# P7_CCD_CAM_BOARD_MYIR.net
KiCad netlist of a schematic drawn in Altium Designer
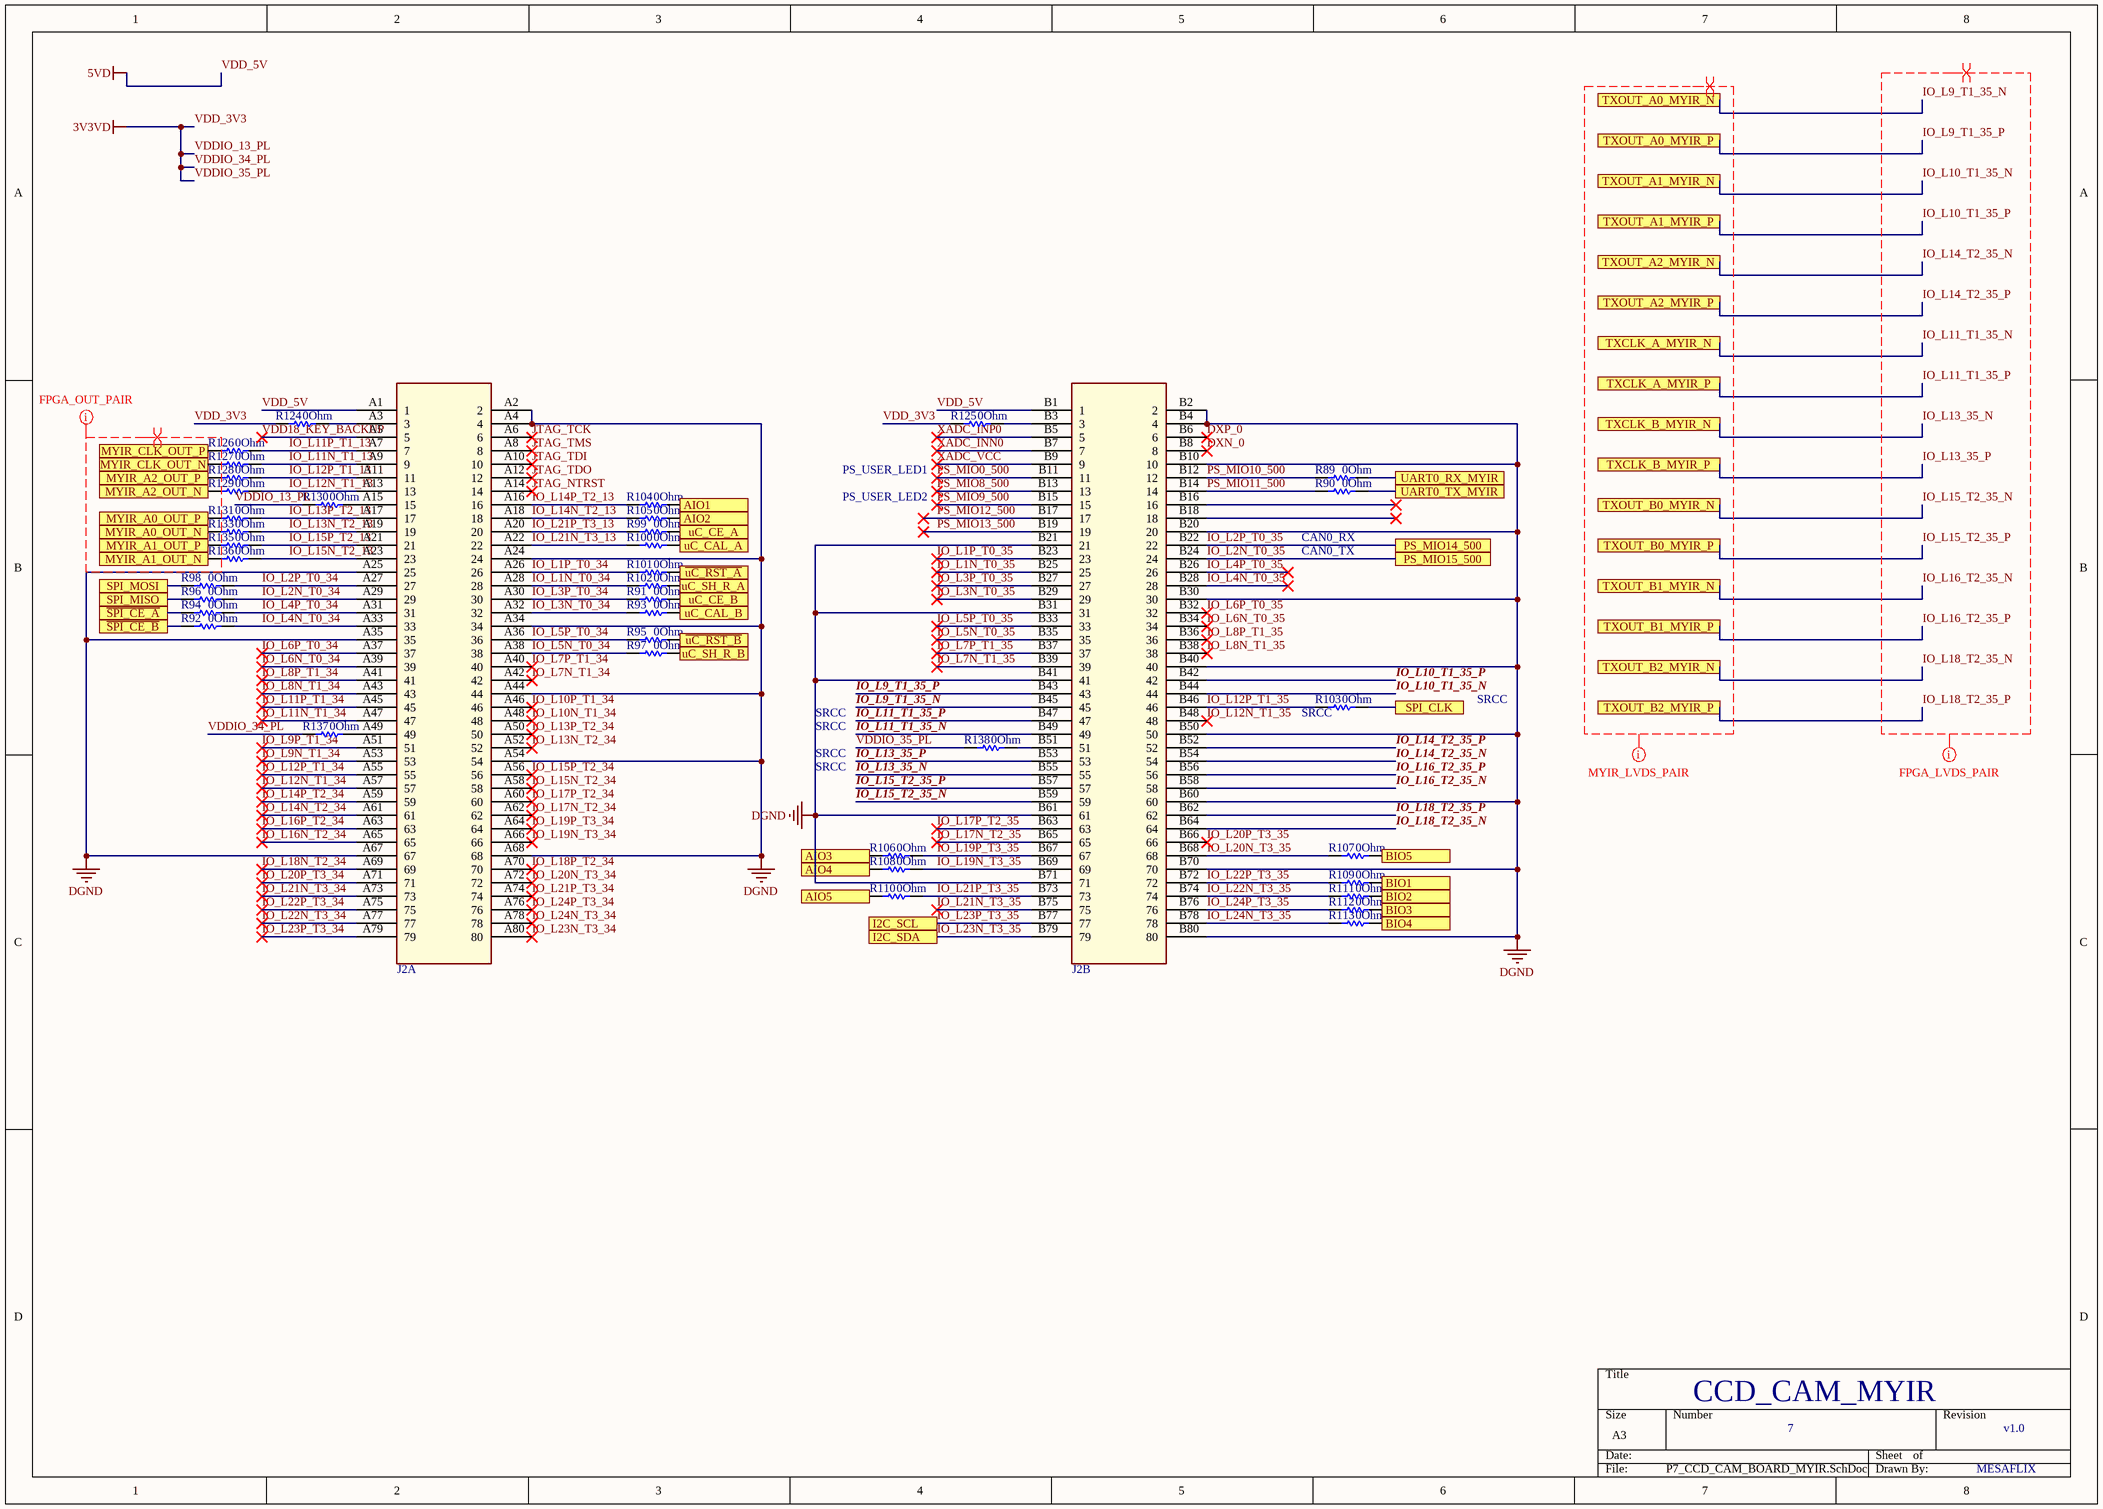
[diagram p0: P7_CCD_CAM_BOARD_MYIR.SchDoc]

(export (version "E")
  (design (tool "Eeschema 10.0.6"))
  (components
    (comp (ref "J2")
      (value "40x2 Connector 1.27mm Pitch")
      (footprint "CON2x80_MYIR_SMD")
      (fields
        (field (name "MANUFACTURER PART NUMBER") "20021121-00080T4LF")
        (field (name "DIGIKEY PART NUMBER") "609-3741-ND")
      )
      (libsource (lib "CCD_CAM_BOARD") (part "CON_40x2_MYIR_ZTURN"))
    )
    (comp (ref "R89")
      (value "0Ohm")
      (footprint "R 0402(1005)")
      (fields
        (field (name "DIGIKEYPARTNUMBER") "311-0.0LDCT-ND")
        (field (name "MANUFACTURER") "Yageo")
        (field (name "MANUFACTURERPARTNUMBER") "AC0603FR-070RL")
      )
      (libsource (lib "TESLA_PCB_LIB") (part "RES_1K_0603"))
    )
    (comp (ref "R90")
      (value "0Ohm")
      (footprint "R 0402(1005)")
      (fields
        (field (name "DIGIKEYPARTNUMBER") "311-0.0LDCT-ND")
        (field (name "MANUFACTURER") "Yageo")
        (field (name "MANUFACTURERPARTNUMBER") "AC0603FR-070RL")
      )
      (libsource (lib "TESLA_PCB_LIB") (part "RES_1K_0603"))
    )
    (comp (ref "R91")
      (value "0Ohm")
      (footprint "R 0402(1005)")
      (fields
        (field (name "DIGIKEYPARTNUMBER") "311-0.0LDCT-ND")
        (field (name "MANUFACTURER") "Yageo")
        (field (name "MANUFACTURERPARTNUMBER") "AC0603FR-070RL")
      )
      (libsource (lib "TESLA_PCB_LIB") (part "RES_1K_0603"))
    )
    (comp (ref "R92")
      (value "0Ohm")
      (footprint "R 0402(1005)")
      (fields
        (field (name "DIGIKEYPARTNUMBER") "311-0.0LDCT-ND")
        (field (name "MANUFACTURER") "Yageo")
        (field (name "MANUFACTURERPARTNUMBER") "AC0603FR-070RL")
      )
      (libsource (lib "TESLA_PCB_LIB") (part "RES_1K_0603"))
    )
    (comp (ref "R93")
      (value "0Ohm")
      (footprint "R 0402(1005)")
      (fields
        (field (name "DIGIKEYPARTNUMBER") "311-0.0LDCT-ND")
        (field (name "MANUFACTURER") "Yageo")
        (field (name "MANUFACTURERPARTNUMBER") "AC0603FR-070RL")
      )
      (libsource (lib "TESLA_PCB_LIB") (part "RES_1K_0603"))
    )
    (comp (ref "R94")
      (value "0Ohm")
      (footprint "R 0402(1005)")
      (fields
        (field (name "DIGIKEYPARTNUMBER") "311-0.0LDCT-ND")
        (field (name "MANUFACTURER") "Yageo")
        (field (name "MANUFACTURERPARTNUMBER") "AC0603FR-070RL")
      )
      (libsource (lib "TESLA_PCB_LIB") (part "RES_1K_0603"))
    )
    (comp (ref "R95")
      (value "0Ohm")
      (footprint "R 0402(1005)")
      (fields
        (field (name "DIGIKEYPARTNUMBER") "311-0.0LDCT-ND")
        (field (name "MANUFACTURER") "Yageo")
        (field (name "MANUFACTURERPARTNUMBER") "AC0603FR-070RL")
      )
      (libsource (lib "TESLA_PCB_LIB") (part "RES_1K_0603"))
    )
    (comp (ref "R96")
      (value "0Ohm")
      (footprint "R 0402(1005)")
      (fields
        (field (name "DIGIKEYPARTNUMBER") "311-0.0LDCT-ND")
        (field (name "MANUFACTURER") "Yageo")
        (field (name "MANUFACTURERPARTNUMBER") "AC0603FR-070RL")
      )
      (libsource (lib "TESLA_PCB_LIB") (part "RES_1K_0603"))
    )
    (comp (ref "R97")
      (value "0Ohm")
      (footprint "R 0402(1005)")
      (fields
        (field (name "DIGIKEYPARTNUMBER") "311-0.0LDCT-ND")
        (field (name "MANUFACTURER") "Yageo")
        (field (name "MANUFACTURERPARTNUMBER") "AC0603FR-070RL")
      )
      (libsource (lib "TESLA_PCB_LIB") (part "RES_1K_0603"))
    )
    (comp (ref "R98")
      (value "0Ohm")
      (footprint "R 0402(1005)")
      (fields
        (field (name "DIGIKEYPARTNUMBER") "311-0.0LDCT-ND")
        (field (name "MANUFACTURER") "Yageo")
        (field (name "MANUFACTURERPARTNUMBER") "AC0603FR-070RL")
      )
      (libsource (lib "TESLA_PCB_LIB") (part "RES_1K_0603"))
    )
    (comp (ref "R99")
      (value "0Ohm")
      (footprint "R 0402(1005)")
      (fields
        (field (name "DIGIKEYPARTNUMBER") "311-0.0LDCT-ND")
        (field (name "MANUFACTURER") "Yageo")
        (field (name "MANUFACTURERPARTNUMBER") "AC0603FR-070RL")
      )
      (libsource (lib "TESLA_PCB_LIB") (part "RES_1K_0603"))
    )
    (comp (ref "R100")
      (value "0Ohm")
      (footprint "R 0402(1005)")
      (fields
        (field (name "DIGIKEYPARTNUMBER") "311-0.0LDCT-ND")
        (field (name "MANUFACTURER") "Yageo")
        (field (name "MANUFACTURERPARTNUMBER") "AC0603FR-070RL")
      )
      (libsource (lib "TESLA_PCB_LIB") (part "RES_1K_0603"))
    )
    (comp (ref "R101")
      (value "0Ohm")
      (footprint "R 0402(1005)")
      (fields
        (field (name "DIGIKEYPARTNUMBER") "311-0.0LDCT-ND")
        (field (name "MANUFACTURER") "Yageo")
        (field (name "MANUFACTURERPARTNUMBER") "AC0603FR-070RL")
      )
      (libsource (lib "TESLA_PCB_LIB") (part "RES_1K_0603"))
    )
    (comp (ref "R102")
      (value "0Ohm")
      (footprint "R 0402(1005)")
      (fields
        (field (name "DIGIKEYPARTNUMBER") "311-0.0LDCT-ND")
        (field (name "MANUFACTURER") "Yageo")
        (field (name "MANUFACTURERPARTNUMBER") "AC0603FR-070RL")
      )
      (libsource (lib "TESLA_PCB_LIB") (part "RES_1K_0603"))
    )
    (comp (ref "R103")
      (value "0Ohm")
      (footprint "R 0402(1005)")
      (fields
        (field (name "DIGIKEYPARTNUMBER") "311-0.0LDCT-ND")
        (field (name "MANUFACTURER") "Yageo")
        (field (name "MANUFACTURERPARTNUMBER") "AC0603FR-070RL")
      )
      (libsource (lib "TESLA_PCB_LIB") (part "RES_1K_0603"))
    )
    (comp (ref "R104")
      (value "0Ohm")
      (footprint "R 0402(1005)")
      (fields
        (field (name "DIGIKEYPARTNUMBER") "311-0.0LDCT-ND")
        (field (name "MANUFACTURER") "Yageo")
        (field (name "MANUFACTURERPARTNUMBER") "AC0603FR-070RL")
      )
      (libsource (lib "TESLA_PCB_LIB") (part "RES_1K_0603"))
    )
    (comp (ref "R105")
      (value "0Ohm")
      (footprint "R 0402(1005)")
      (fields
        (field (name "DIGIKEYPARTNUMBER") "311-0.0LDCT-ND")
        (field (name "MANUFACTURER") "Yageo")
        (field (name "MANUFACTURERPARTNUMBER") "AC0603FR-070RL")
      )
      (libsource (lib "TESLA_PCB_LIB") (part "RES_1K_0603"))
    )
    (comp (ref "R106")
      (value "0Ohm")
      (footprint "R 0402(1005)")
      (fields
        (field (name "DIGIKEYPARTNUMBER") "311-0.0LDCT-ND")
        (field (name "MANUFACTURER") "Yageo")
        (field (name "MANUFACTURERPARTNUMBER") "AC0603FR-070RL")
      )
      (libsource (lib "TESLA_PCB_LIB") (part "RES_1K_0603"))
    )
    (comp (ref "R107")
      (value "0Ohm")
      (footprint "R 0402(1005)")
      (fields
        (field (name "DIGIKEYPARTNUMBER") "311-0.0LDCT-ND")
        (field (name "MANUFACTURER") "Yageo")
        (field (name "MANUFACTURERPARTNUMBER") "AC0603FR-070RL")
      )
      (libsource (lib "TESLA_PCB_LIB") (part "RES_1K_0603"))
    )
    (comp (ref "R108")
      (value "0Ohm")
      (footprint "R 0402(1005)")
      (fields
        (field (name "DIGIKEYPARTNUMBER") "311-0.0LDCT-ND")
        (field (name "MANUFACTURER") "Yageo")
        (field (name "MANUFACTURERPARTNUMBER") "AC0603FR-070RL")
      )
      (libsource (lib "TESLA_PCB_LIB") (part "RES_1K_0603"))
    )
    (comp (ref "R109")
      (value "0Ohm")
      (footprint "R 0402(1005)")
      (fields
        (field (name "DIGIKEYPARTNUMBER") "311-0.0LDCT-ND")
        (field (name "MANUFACTURER") "Yageo")
        (field (name "MANUFACTURERPARTNUMBER") "AC0603FR-070RL")
      )
      (libsource (lib "TESLA_PCB_LIB") (part "RES_1K_0603"))
    )
    (comp (ref "R110")
      (value "0Ohm")
      (footprint "R 0402(1005)")
      (fields
        (field (name "DIGIKEYPARTNUMBER") "311-0.0LDCT-ND")
        (field (name "MANUFACTURER") "Yageo")
        (field (name "MANUFACTURERPARTNUMBER") "AC0603FR-070RL")
      )
      (libsource (lib "TESLA_PCB_LIB") (part "RES_1K_0603"))
    )
    (comp (ref "R111")
      (value "0Ohm")
      (footprint "R 0402(1005)")
      (fields
        (field (name "DIGIKEYPARTNUMBER") "311-0.0LDCT-ND")
        (field (name "MANUFACTURER") "Yageo")
        (field (name "MANUFACTURERPARTNUMBER") "AC0603FR-070RL")
      )
      (libsource (lib "TESLA_PCB_LIB") (part "RES_1K_0603"))
    )
    (comp (ref "R112")
      (value "0Ohm")
      (footprint "R 0402(1005)")
      (fields
        (field (name "DIGIKEYPARTNUMBER") "311-0.0LDCT-ND")
        (field (name "MANUFACTURER") "Yageo")
        (field (name "MANUFACTURERPARTNUMBER") "AC0603FR-070RL")
      )
      (libsource (lib "TESLA_PCB_LIB") (part "RES_1K_0603"))
    )
    (comp (ref "R113")
      (value "0Ohm")
      (footprint "R 0402(1005)")
      (fields
        (field (name "DIGIKEYPARTNUMBER") "311-0.0LDCT-ND")
        (field (name "MANUFACTURER") "Yageo")
        (field (name "MANUFACTURERPARTNUMBER") "AC0603FR-070RL")
      )
      (libsource (lib "TESLA_PCB_LIB") (part "RES_1K_0603"))
    )
    (comp (ref "R124")
      (value "0Ohm")
      (footprint "R 0402(1005)")
      (fields
        (field (name "DIGIKEYPARTNUMBER") "311-0.0LDCT-ND")
        (field (name "MANUFACTURER") "Yageo")
        (field (name "MANUFACTURERPARTNUMBER") "AC0603FR-070RL")
      )
      (libsource (lib "TESLA_PCB_LIB") (part "RES_1K_0603"))
    )
    (comp (ref "R125")
      (value "0Ohm")
      (footprint "R 0402(1005)")
      (fields
        (field (name "DIGIKEYPARTNUMBER") "311-0.0LDCT-ND")
        (field (name "MANUFACTURER") "Yageo")
        (field (name "MANUFACTURERPARTNUMBER") "AC0603FR-070RL")
      )
      (libsource (lib "TESLA_PCB_LIB") (part "RES_1K_0603"))
    )
    (comp (ref "R126")
      (value "0Ohm")
      (footprint "R 0402(1005)")
      (fields
        (field (name "DIGIKEYPARTNUMBER") "311-0.0LDCT-ND")
        (field (name "MANUFACTURER") "Yageo")
        (field (name "MANUFACTURERPARTNUMBER") "AC0603FR-070RL")
      )
      (libsource (lib "TESLA_PCB_LIB") (part "RES_1K_0603"))
    )
    (comp (ref "R127")
      (value "0Ohm")
      (footprint "R 0402(1005)")
      (fields
        (field (name "DIGIKEYPARTNUMBER") "311-0.0LDCT-ND")
        (field (name "MANUFACTURER") "Yageo")
        (field (name "MANUFACTURERPARTNUMBER") "AC0603FR-070RL")
      )
      (libsource (lib "TESLA_PCB_LIB") (part "RES_1K_0603"))
    )
    (comp (ref "R128")
      (value "0Ohm")
      (footprint "R 0402(1005)")
      (fields
        (field (name "DIGIKEYPARTNUMBER") "311-0.0LDCT-ND")
        (field (name "MANUFACTURER") "Yageo")
        (field (name "MANUFACTURERPARTNUMBER") "AC0603FR-070RL")
      )
      (libsource (lib "TESLA_PCB_LIB") (part "RES_1K_0603"))
    )
    (comp (ref "R129")
      (value "0Ohm")
      (footprint "R 0402(1005)")
      (fields
        (field (name "DIGIKEYPARTNUMBER") "311-0.0LDCT-ND")
        (field (name "MANUFACTURER") "Yageo")
        (field (name "MANUFACTURERPARTNUMBER") "AC0603FR-070RL")
      )
      (libsource (lib "TESLA_PCB_LIB") (part "RES_1K_0603"))
    )
    (comp (ref "R130")
      (value "0Ohm")
      (footprint "R 0402(1005)")
      (fields
        (field (name "DIGIKEYPARTNUMBER") "311-0.0LDCT-ND")
        (field (name "MANUFACTURER") "Yageo")
        (field (name "MANUFACTURERPARTNUMBER") "AC0603FR-070RL")
      )
      (libsource (lib "TESLA_PCB_LIB") (part "RES_1K_0603"))
    )
    (comp (ref "R131")
      (value "0Ohm")
      (footprint "R 0402(1005)")
      (fields
        (field (name "DIGIKEYPARTNUMBER") "311-0.0LDCT-ND")
        (field (name "MANUFACTURER") "Yageo")
        (field (name "MANUFACTURERPARTNUMBER") "AC0603FR-070RL")
      )
      (libsource (lib "TESLA_PCB_LIB") (part "RES_1K_0603"))
    )
    (comp (ref "R133")
      (value "0Ohm")
      (footprint "R 0402(1005)")
      (fields
        (field (name "DIGIKEYPARTNUMBER") "311-0.0LDCT-ND")
        (field (name "MANUFACTURER") "Yageo")
        (field (name "MANUFACTURERPARTNUMBER") "AC0603FR-070RL")
      )
      (libsource (lib "TESLA_PCB_LIB") (part "RES_1K_0603"))
    )
    (comp (ref "R135")
      (value "0Ohm")
      (footprint "R 0402(1005)")
      (fields
        (field (name "DIGIKEYPARTNUMBER") "311-0.0LDCT-ND")
        (field (name "MANUFACTURER") "Yageo")
        (field (name "MANUFACTURERPARTNUMBER") "AC0603FR-070RL")
      )
      (libsource (lib "TESLA_PCB_LIB") (part "RES_1K_0603"))
    )
    (comp (ref "R136")
      (value "0Ohm")
      (footprint "R 0402(1005)")
      (fields
        (field (name "DIGIKEYPARTNUMBER") "311-0.0LDCT-ND")
        (field (name "MANUFACTURER") "Yageo")
        (field (name "MANUFACTURERPARTNUMBER") "AC0603FR-070RL")
      )
      (libsource (lib "TESLA_PCB_LIB") (part "RES_1K_0603"))
    )
    (comp (ref "R137")
      (value "0Ohm")
      (footprint "R 0402(1005)")
      (fields
        (field (name "DIGIKEYPARTNUMBER") "311-0.0LDCT-ND")
        (field (name "MANUFACTURER") "Yageo")
        (field (name "MANUFACTURERPARTNUMBER") "AC0603FR-070RL")
      )
      (libsource (lib "TESLA_PCB_LIB") (part "RES_1K_0603"))
    )
    (comp (ref "R138")
      (value "0Ohm")
      (footprint "R 0402(1005)")
      (fields
        (field (name "DIGIKEYPARTNUMBER") "311-0.0LDCT-ND")
        (field (name "MANUFACTURER") "Yageo")
        (field (name "MANUFACTURERPARTNUMBER") "AC0603FR-070RL")
      )
      (libsource (lib "TESLA_PCB_LIB") (part "RES_1K_0603"))
    )
  )
  (nets
    (net (code "1") (name "/AIO1") (class "Default")
      (node (ref "R104") (pin "2") (pinfunction "2_2") (pintype "passive"))
    )
    (net (code "2") (name "/AIO2") (class "Default")
      (node (ref "R105") (pin "2") (pinfunction "2_2") (pintype "passive"))
    )
    (net (code "3") (name "/AIO3") (class "Default")
      (node (ref "R106") (pin "1") (pinfunction "1_1") (pintype "passive"))
    )
    (net (code "4") (name "/AIO4") (class "Default")
      (node (ref "R108") (pin "1") (pinfunction "1_1") (pintype "passive"))
    )
    (net (code "5") (name "/AIO5") (class "Default")
      (node (ref "R110") (pin "1") (pinfunction "1_1") (pintype "passive"))
    )
    (net (code "6") (name "/BIO1") (class "Default")
      (node (ref "R109") (pin "2") (pinfunction "2_2") (pintype "passive"))
    )
    (net (code "7") (name "/BIO2") (class "Default")
      (node (ref "R111") (pin "2") (pinfunction "2_2") (pintype "passive"))
    )
    (net (code "8") (name "/BIO3") (class "Default")
      (node (ref "R112") (pin "2") (pinfunction "2_2") (pintype "passive"))
    )
    (net (code "9") (name "/BIO4") (class "Default")
      (node (ref "R113") (pin "2") (pinfunction "2_2") (pintype "passive"))
    )
    (net (code "10") (name "/BIO5") (class "Default")
      (node (ref "R107") (pin "2") (pinfunction "2_2") (pintype "passive"))
    )
    (net (code "11") (name "/DXN_0") (class "Default")
      (node (ref "J2") (pin "B8") (pinfunction "8_B8") (pintype "passive+no_connect"))
    )
    (net (code "12") (name "/DXP_0") (class "Default")
      (node (ref "J2") (pin "B6") (pinfunction "6_B6") (pintype "passive+no_connect"))
    )
    (net (code "13") (name "/IO_L1N_T0_34") (class "Default")
      (node (ref "J2") (pin "A28") (pinfunction "28_A28") (pintype "passive"))
      (node (ref "R102") (pin "1") (pinfunction "1_1") (pintype "passive"))
    )
    (net (code "14") (name "/IO_L1N_T0_35") (class "Default")
      (node (ref "J2") (pin "B25") (pinfunction "25_B25") (pintype "passive+no_connect"))
    )
    (net (code "15") (name "/IO_L1P_T0_34") (class "Default")
      (node (ref "J2") (pin "A26") (pinfunction "26_A26") (pintype "passive"))
      (node (ref "R101") (pin "1") (pinfunction "1_1") (pintype "passive"))
    )
    (net (code "16") (name "/IO_L1P_T0_35") (class "Default")
      (node (ref "J2") (pin "B23") (pinfunction "23_B23") (pintype "passive+no_connect"))
    )
    (net (code "17") (name "/IO_L2N_T0_34") (class "Default")
      (node (ref "J2") (pin "A29") (pinfunction "29_A29") (pintype "passive"))
      (node (ref "R96") (pin "2") (pinfunction "2_2") (pintype "passive"))
    )
    (net (code "18") (name "/IO_L2N_T0_35") (class "Default")
      (node (ref "J2") (pin "B24") (pinfunction "24_B24") (pintype "passive"))
    )
    (net (code "19") (name "/IO_L2P_T0_34") (class "Default")
      (node (ref "J2") (pin "A27") (pinfunction "27_A27") (pintype "passive"))
      (node (ref "R98") (pin "2") (pinfunction "2_2") (pintype "passive"))
    )
    (net (code "20") (name "/IO_L2P_T0_35") (class "Default")
      (node (ref "J2") (pin "B22") (pinfunction "22_B22") (pintype "passive"))
    )
    (net (code "21") (name "/IO_L3N_T0_34") (class "Default")
      (node (ref "J2") (pin "A32") (pinfunction "32_A32") (pintype "passive"))
      (node (ref "R93") (pin "1") (pinfunction "1_1") (pintype "passive"))
    )
    (net (code "22") (name "/IO_L3N_T0_35") (class "Default")
      (node (ref "J2") (pin "B29") (pinfunction "29_B29") (pintype "passive+no_connect"))
    )
    (net (code "23") (name "/IO_L3P_T0_34") (class "Default")
      (node (ref "J2") (pin "A30") (pinfunction "30_A30") (pintype "passive"))
      (node (ref "R91") (pin "1") (pinfunction "1_1") (pintype "passive"))
    )
    (net (code "24") (name "/IO_L3P_T0_35") (class "Default")
      (node (ref "J2") (pin "B27") (pinfunction "27_B27") (pintype "passive+no_connect"))
    )
    (net (code "25") (name "/IO_L4N_T0_34") (class "Default")
      (node (ref "J2") (pin "A33") (pinfunction "33_A33") (pintype "passive"))
      (node (ref "R92") (pin "2") (pinfunction "2_2") (pintype "passive"))
    )
    (net (code "26") (name "/IO_L4N_T0_35") (class "Default")
      (node (ref "J2") (pin "B28") (pinfunction "28_B28") (pintype "passive+no_connect"))
    )
    (net (code "27") (name "/IO_L4P_T0_34") (class "Default")
      (node (ref "J2") (pin "A31") (pinfunction "31_A31") (pintype "passive"))
      (node (ref "R94") (pin "2") (pinfunction "2_2") (pintype "passive"))
    )
    (net (code "28") (name "/IO_L4P_T0_35") (class "Default")
      (node (ref "J2") (pin "B26") (pinfunction "26_B26") (pintype "passive+no_connect"))
    )
    (net (code "29") (name "/IO_L5N_T0_34") (class "Default")
      (node (ref "J2") (pin "A38") (pinfunction "38_A38") (pintype "passive"))
      (node (ref "R97") (pin "1") (pinfunction "1_1") (pintype "passive"))
    )
    (net (code "30") (name "/IO_L5N_T0_35") (class "Default")
      (node (ref "J2") (pin "B35") (pinfunction "35_B35") (pintype "passive+no_connect"))
    )
    (net (code "31") (name "/IO_L5P_T0_34") (class "Default")
      (node (ref "J2") (pin "A36") (pinfunction "36_A36") (pintype "passive"))
      (node (ref "R95") (pin "1") (pinfunction "1_1") (pintype "passive"))
    )
    (net (code "32") (name "/IO_L5P_T0_35") (class "Default")
      (node (ref "J2") (pin "B33") (pinfunction "33_B33") (pintype "passive+no_connect"))
    )
    (net (code "33") (name "/IO_L6N_T0_34") (class "Default")
      (node (ref "J2") (pin "A39") (pinfunction "39_A39") (pintype "passive+no_connect"))
    )
    (net (code "34") (name "/IO_L6N_T0_35") (class "Default")
      (node (ref "J2") (pin "B34") (pinfunction "34_B34") (pintype "passive+no_connect"))
    )
    (net (code "35") (name "/IO_L6P_T0_34") (class "Default")
      (node (ref "J2") (pin "A37") (pinfunction "37_A37") (pintype "passive+no_connect"))
    )
    (net (code "36") (name "/IO_L6P_T0_35") (class "Default")
      (node (ref "J2") (pin "B32") (pinfunction "32_B32") (pintype "passive+no_connect"))
    )
    (net (code "37") (name "/IO_L7N_T1_34") (class "Default")
      (node (ref "J2") (pin "A42") (pinfunction "42_A42") (pintype "passive+no_connect"))
    )
    (net (code "38") (name "/IO_L7N_T1_35") (class "Default")
      (node (ref "J2") (pin "B39") (pinfunction "39_B39") (pintype "passive+no_connect"))
    )
    (net (code "39") (name "/IO_L7P_T1_34") (class "Default")
      (node (ref "J2") (pin "A40") (pinfunction "40_A40") (pintype "passive+no_connect"))
    )
    (net (code "40") (name "/IO_L7P_T1_35") (class "Default")
      (node (ref "J2") (pin "B37") (pinfunction "37_B37") (pintype "passive+no_connect"))
    )
    (net (code "41") (name "/IO_L8N_T1_34") (class "Default")
      (node (ref "J2") (pin "A43") (pinfunction "43_A43") (pintype "passive+no_connect"))
    )
    (net (code "42") (name "/IO_L8N_T1_35") (class "Default")
      (node (ref "J2") (pin "B38") (pinfunction "38_B38") (pintype "passive+no_connect"))
    )
    (net (code "43") (name "/IO_L8P_T1_34") (class "Default")
      (node (ref "J2") (pin "A41") (pinfunction "41_A41") (pintype "passive+no_connect"))
    )
    (net (code "44") (name "/IO_L8P_T1_35") (class "Default")
      (node (ref "J2") (pin "B36") (pinfunction "36_B36") (pintype "passive+no_connect"))
    )
    (net (code "45") (name "/IO_L9N_T1_34") (class "Default")
      (node (ref "J2") (pin "A53") (pinfunction "53_A53") (pintype "passive+no_connect"))
    )
    (net (code "46") (name "/IO_L9P_T1_34") (class "Default")
      (node (ref "J2") (pin "A51") (pinfunction "51_A51") (pintype "passive+no_connect"))
    )
    (net (code "47") (name "/IO_L9_T1_35_N") (class "Default")
      (node (ref "J2") (pin "B45") (pinfunction "45_B45") (pintype "passive"))
    )
    (net (code "48") (name "/IO_L9_T1_35_P") (class "Default")
      (node (ref "J2") (pin "B43") (pinfunction "43_B43") (pintype "passive"))
    )
    (net (code "49") (name "/IO_L10N_T1_34") (class "Default")
      (node (ref "J2") (pin "A48") (pinfunction "48_A48") (pintype "passive+no_connect"))
    )
    (net (code "50") (name "/IO_L10P_T1_34") (class "Default")
      (node (ref "J2") (pin "A46") (pinfunction "46_A46") (pintype "passive+no_connect"))
    )
    (net (code "51") (name "/IO_L10_T1_35_N") (class "Default")
      (node (ref "J2") (pin "B44") (pinfunction "44_B44") (pintype "passive"))
    )
    (net (code "52") (name "/IO_L10_T1_35_P") (class "Default")
      (node (ref "J2") (pin "B42") (pinfunction "42_B42") (pintype "passive"))
    )
    (net (code "53") (name "/IO_L11N_T1_13") (class "Default")
      (node (ref "J2") (pin "A9") (pinfunction "9_A9") (pintype "passive"))
      (node (ref "R127") (pin "2") (pinfunction "2_2") (pintype "passive"))
    )
    (net (code "54") (name "/IO_L11N_T1_34") (class "Default")
      (node (ref "J2") (pin "A47") (pinfunction "47_A47") (pintype "passive+no_connect"))
    )
    (net (code "55") (name "/IO_L11P_T1_13") (class "Default")
      (node (ref "J2") (pin "A7") (pinfunction "7_A7") (pintype "passive"))
      (node (ref "R126") (pin "2") (pinfunction "2_2") (pintype "passive"))
    )
    (net (code "56") (name "/IO_L11P_T1_34") (class "Default")
      (node (ref "J2") (pin "A45") (pinfunction "45_A45") (pintype "passive+no_connect"))
    )
    (net (code "57") (name "/IO_L11_T1_35_N") (class "Default")
      (node (ref "J2") (pin "B49") (pinfunction "49_B49") (pintype "passive"))
    )
    (net (code "58") (name "/IO_L11_T1_35_P") (class "Default")
      (node (ref "J2") (pin "B47") (pinfunction "47_B47") (pintype "passive"))
    )
    (net (code "59") (name "/IO_L12N_T1_13") (class "Default")
      (node (ref "J2") (pin "A13") (pinfunction "13_A13") (pintype "passive"))
      (node (ref "R129") (pin "2") (pinfunction "2_2") (pintype "passive"))
    )
    (net (code "60") (name "/IO_L12N_T1_34") (class "Default")
      (node (ref "J2") (pin "A57") (pinfunction "57_A57") (pintype "passive+no_connect"))
    )
    (net (code "61") (name "/IO_L12N_T1_35") (class "Default")
      (node (ref "J2") (pin "B48") (pinfunction "48_B48") (pintype "passive+no_connect"))
    )
    (net (code "62") (name "/IO_L12P_T1_13") (class "Default")
      (node (ref "J2") (pin "A11") (pinfunction "11_A11") (pintype "passive"))
      (node (ref "R128") (pin "2") (pinfunction "2_2") (pintype "passive"))
    )
    (net (code "63") (name "/IO_L12P_T1_34") (class "Default")
      (node (ref "J2") (pin "A55") (pinfunction "55_A55") (pintype "passive+no_connect"))
    )
    (net (code "64") (name "/IO_L12P_T1_35") (class "Default")
      (node (ref "J2") (pin "B46") (pinfunction "46_B46") (pintype "passive"))
      (node (ref "R103") (pin "1") (pinfunction "1_1") (pintype "passive"))
    )
    (net (code "65") (name "/IO_L13N_T2_13") (class "Default")
      (node (ref "J2") (pin "A19") (pinfunction "19_A19") (pintype "passive"))
      (node (ref "R133") (pin "2") (pinfunction "2_2") (pintype "passive"))
    )
    (net (code "66") (name "/IO_L13N_T2_34") (class "Default")
      (node (ref "J2") (pin "A52") (pinfunction "52_A52") (pintype "passive+no_connect"))
    )
    (net (code "67") (name "/IO_L13P_T2_13") (class "Default")
      (node (ref "J2") (pin "A17") (pinfunction "17_A17") (pintype "passive"))
      (node (ref "R131") (pin "2") (pinfunction "2_2") (pintype "passive"))
    )
    (net (code "68") (name "/IO_L13P_T2_34") (class "Default")
      (node (ref "J2") (pin "A50") (pinfunction "50_A50") (pintype "passive+no_connect"))
    )
    (net (code "69") (name "/IO_L13_35_N") (class "Default")
      (node (ref "J2") (pin "B55") (pinfunction "55_B55") (pintype "passive"))
    )
    (net (code "70") (name "/IO_L13_35_P") (class "Default")
      (node (ref "J2") (pin "B53") (pinfunction "53_B53") (pintype "passive"))
    )
    (net (code "71") (name "/IO_L14N_T2_13") (class "Default")
      (node (ref "J2") (pin "A18") (pinfunction "18_A18") (pintype "passive"))
      (node (ref "R105") (pin "1") (pinfunction "1_1") (pintype "passive"))
    )
    (net (code "72") (name "/IO_L14N_T2_34") (class "Default")
      (node (ref "J2") (pin "A61") (pinfunction "61_A61") (pintype "passive+no_connect"))
    )
    (net (code "73") (name "/IO_L14P_T2_13") (class "Default")
      (node (ref "J2") (pin "A16") (pinfunction "16_A16") (pintype "passive"))
      (node (ref "R104") (pin "1") (pinfunction "1_1") (pintype "passive"))
    )
    (net (code "74") (name "/IO_L14P_T2_34") (class "Default")
      (node (ref "J2") (pin "A59") (pinfunction "59_A59") (pintype "passive+no_connect"))
    )
    (net (code "75") (name "/IO_L14_T2_35_N") (class "Default")
      (node (ref "J2") (pin "B54") (pinfunction "54_B54") (pintype "passive"))
    )
    (net (code "76") (name "/IO_L14_T2_35_P") (class "Default")
      (node (ref "J2") (pin "B52") (pinfunction "52_B52") (pintype "passive"))
    )
    (net (code "77") (name "/IO_L15N_T2_13") (class "Default")
      (node (ref "J2") (pin "A23") (pinfunction "23_A23") (pintype "passive"))
      (node (ref "R136") (pin "2") (pinfunction "2_2") (pintype "passive"))
    )
    (net (code "78") (name "/IO_L15N_T2_34") (class "Default")
      (node (ref "J2") (pin "A58") (pinfunction "58_A58") (pintype "passive+no_connect"))
    )
    (net (code "79") (name "/IO_L15P_T2_13") (class "Default")
      (node (ref "J2") (pin "A21") (pinfunction "21_A21") (pintype "passive"))
      (node (ref "R135") (pin "2") (pinfunction "2_2") (pintype "passive"))
    )
    (net (code "80") (name "/IO_L15P_T2_34") (class "Default")
      (node (ref "J2") (pin "A56") (pinfunction "56_A56") (pintype "passive+no_connect"))
    )
    (net (code "81") (name "/IO_L15_T2_35_N") (class "Default")
      (node (ref "J2") (pin "B59") (pinfunction "59_B59") (pintype "passive"))
    )
    (net (code "82") (name "/IO_L15_T2_35_P") (class "Default")
      (node (ref "J2") (pin "B57") (pinfunction "57_B57") (pintype "passive"))
    )
    (net (code "83") (name "/IO_L16N_T2_34") (class "Default")
      (node (ref "J2") (pin "A65") (pinfunction "65_A65") (pintype "passive+no_connect"))
    )
    (net (code "84") (name "/IO_L16P_T2_34") (class "Default")
      (node (ref "J2") (pin "A63") (pinfunction "63_A63") (pintype "passive+no_connect"))
    )
    (net (code "85") (name "/IO_L16_T2_35_N") (class "Default")
      (node (ref "J2") (pin "B58") (pinfunction "58_B58") (pintype "passive"))
    )
    (net (code "86") (name "/IO_L16_T2_35_P") (class "Default")
      (node (ref "J2") (pin "B56") (pinfunction "56_B56") (pintype "passive"))
    )
    (net (code "87") (name "/IO_L17N_T2_34") (class "Default")
      (node (ref "J2") (pin "A62") (pinfunction "62_A62") (pintype "passive+no_connect"))
    )
    (net (code "88") (name "/IO_L17N_T2_35") (class "Default")
      (node (ref "J2") (pin "B65") (pinfunction "65_B65") (pintype "passive+no_connect"))
    )
    (net (code "89") (name "/IO_L17P_T2_34") (class "Default")
      (node (ref "J2") (pin "A60") (pinfunction "60_A60") (pintype "passive+no_connect"))
    )
    (net (code "90") (name "/IO_L17P_T2_35") (class "Default")
      (node (ref "J2") (pin "B63") (pinfunction "63_B63") (pintype "passive+no_connect"))
    )
    (net (code "91") (name "/IO_L18N_T2_34") (class "Default")
      (node (ref "J2") (pin "A69") (pinfunction "69_A69") (pintype "passive+no_connect"))
    )
    (net (code "92") (name "/IO_L18P_T2_34") (class "Default")
      (node (ref "J2") (pin "A70") (pinfunction "70_A70") (pintype "passive+no_connect"))
    )
    (net (code "93") (name "/IO_L18_T2_35_N") (class "Default")
      (node (ref "J2") (pin "B64") (pinfunction "64_B64") (pintype "passive"))
    )
    (net (code "94") (name "/IO_L18_T2_35_P") (class "Default")
      (node (ref "J2") (pin "B62") (pinfunction "62_B62") (pintype "passive"))
    )
    (net (code "95") (name "/IO_L19N_T3_34") (class "Default")
      (node (ref "J2") (pin "A66") (pinfunction "66_A66") (pintype "passive+no_connect"))
    )
    (net (code "96") (name "/IO_L19N_T3_35") (class "Default")
      (node (ref "J2") (pin "B69") (pinfunction "69_B69") (pintype "passive"))
      (node (ref "R108") (pin "2") (pinfunction "2_2") (pintype "passive"))
    )
    (net (code "97") (name "/IO_L19P_T3_34") (class "Default")
      (node (ref "J2") (pin "A64") (pinfunction "64_A64") (pintype "passive+no_connect"))
    )
    (net (code "98") (name "/IO_L19P_T3_35") (class "Default")
      (node (ref "J2") (pin "B67") (pinfunction "67_B67") (pintype "passive"))
      (node (ref "R106") (pin "2") (pinfunction "2_2") (pintype "passive"))
    )
    (net (code "99") (name "/IO_L20N_T3_34") (class "Default")
      (node (ref "J2") (pin "A72") (pinfunction "72_A72") (pintype "passive+no_connect"))
    )
    (net (code "100") (name "/IO_L20N_T3_35") (class "Default")
      (node (ref "J2") (pin "B68") (pinfunction "68_B68") (pintype "passive"))
      (node (ref "R107") (pin "1") (pinfunction "1_1") (pintype "passive"))
    )
    (net (code "101") (name "/IO_L20P_T3_34") (class "Default")
      (node (ref "J2") (pin "A71") (pinfunction "71_A71") (pintype "passive+no_connect"))
    )
    (net (code "102") (name "/IO_L20P_T3_35") (class "Default")
      (node (ref "J2") (pin "B66") (pinfunction "66_B66") (pintype "passive+no_connect"))
    )
    (net (code "103") (name "/IO_L21N_T3_13") (class "Default")
      (node (ref "J2") (pin "A22") (pinfunction "22_A22") (pintype "passive"))
      (node (ref "R100") (pin "1") (pinfunction "1_1") (pintype "passive"))
    )
    (net (code "104") (name "/IO_L21N_T3_34") (class "Default")
      (node (ref "J2") (pin "A73") (pinfunction "73_A73") (pintype "passive+no_connect"))
    )
    (net (code "105") (name "/IO_L21N_T3_35") (class "Default")
      (node (ref "J2") (pin "B75") (pinfunction "75_B75") (pintype "passive+no_connect"))
    )
    (net (code "106") (name "/IO_L21P_T3_13") (class "Default")
      (node (ref "J2") (pin "A20") (pinfunction "20_A20") (pintype "passive"))
      (node (ref "R99") (pin "1") (pinfunction "1_1") (pintype "passive"))
    )
    (net (code "107") (name "/IO_L21P_T3_34") (class "Default")
      (node (ref "J2") (pin "A74") (pinfunction "74_A74") (pintype "passive+no_connect"))
    )
    (net (code "108") (name "/IO_L21P_T3_35") (class "Default")
      (node (ref "J2") (pin "B73") (pinfunction "73_B73") (pintype "passive"))
      (node (ref "R110") (pin "2") (pinfunction "2_2") (pintype "passive"))
    )
    (net (code "109") (name "/IO_L22N_T3_34") (class "Default")
      (node (ref "J2") (pin "A77") (pinfunction "77_A77") (pintype "passive+no_connect"))
    )
    (net (code "110") (name "/IO_L22N_T3_35") (class "Default")
      (node (ref "J2") (pin "B74") (pinfunction "74_B74") (pintype "passive"))
      (node (ref "R111") (pin "1") (pinfunction "1_1") (pintype "passive"))
    )
    (net (code "111") (name "/IO_L22P_T3_34") (class "Default")
      (node (ref "J2") (pin "A75") (pinfunction "75_A75") (pintype "passive+no_connect"))
    )
    (net (code "112") (name "/IO_L22P_T3_35") (class "Default")
      (node (ref "J2") (pin "B72") (pinfunction "72_B72") (pintype "passive"))
      (node (ref "R109") (pin "1") (pinfunction "1_1") (pintype "passive"))
    )
    (net (code "113") (name "/IO_L23N_T3_34") (class "Default")
      (node (ref "J2") (pin "A80") (pinfunction "80_A80") (pintype "passive+no_connect"))
    )
    (net (code "114") (name "/IO_L23N_T3_35") (class "Default")
      (node (ref "J2") (pin "B79") (pinfunction "79_B79") (pintype "passive"))
    )
    (net (code "115") (name "/IO_L23P_T3_34") (class "Default")
      (node (ref "J2") (pin "A79") (pinfunction "79_A79") (pintype "passive+no_connect"))
    )
    (net (code "116") (name "/IO_L23P_T3_35") (class "Default")
      (node (ref "J2") (pin "B77") (pinfunction "77_B77") (pintype "passive"))
    )
    (net (code "117") (name "/IO_L24N_T3_34") (class "Default")
      (node (ref "J2") (pin "A78") (pinfunction "78_A78") (pintype "passive+no_connect"))
    )
    (net (code "118") (name "/IO_L24N_T3_35") (class "Default")
      (node (ref "J2") (pin "B78") (pinfunction "78_B78") (pintype "passive"))
      (node (ref "R113") (pin "1") (pinfunction "1_1") (pintype "passive"))
    )
    (net (code "119") (name "/IO_L24P_T3_34") (class "Default")
      (node (ref "J2") (pin "A76") (pinfunction "76_A76") (pintype "passive+no_connect"))
    )
    (net (code "120") (name "/IO_L24P_T3_35") (class "Default")
      (node (ref "J2") (pin "B76") (pinfunction "76_B76") (pintype "passive"))
      (node (ref "R112") (pin "1") (pinfunction "1_1") (pintype "passive"))
    )
    (net (code "121") (name "/JTAG_NTRST") (class "Default")
      (node (ref "J2") (pin "A14") (pinfunction "14_A14") (pintype "passive+no_connect"))
    )
    (net (code "122") (name "/JTAG_TCK") (class "Default")
      (node (ref "J2") (pin "A6") (pinfunction "6_A6") (pintype "passive+no_connect"))
    )
    (net (code "123") (name "/JTAG_TDI") (class "Default")
      (node (ref "J2") (pin "A10") (pinfunction "10_A10") (pintype "passive+no_connect"))
    )
    (net (code "124") (name "/JTAG_TDO") (class "Default")
      (node (ref "J2") (pin "A12") (pinfunction "12_A12") (pintype "passive+no_connect"))
    )
    (net (code "125") (name "/JTAG_TMS") (class "Default")
      (node (ref "J2") (pin "A8") (pinfunction "8_A8") (pintype "passive+no_connect"))
    )
    (net (code "126") (name "/MYIR_A0_OUT_N") (class "Default")
      (node (ref "R133") (pin "1") (pinfunction "1_1") (pintype "passive"))
    )
    (net (code "127") (name "/MYIR_A0_OUT_P") (class "Default")
      (node (ref "R131") (pin "1") (pinfunction "1_1") (pintype "passive"))
    )
    (net (code "128") (name "/MYIR_A1_OUT_N") (class "Default")
      (node (ref "R136") (pin "1") (pinfunction "1_1") (pintype "passive"))
    )
    (net (code "129") (name "/MYIR_A1_OUT_P") (class "Default")
      (node (ref "R135") (pin "1") (pinfunction "1_1") (pintype "passive"))
    )
    (net (code "130") (name "/MYIR_A2_OUT_N") (class "Default")
      (node (ref "R129") (pin "1") (pinfunction "1_1") (pintype "passive"))
    )
    (net (code "131") (name "/MYIR_A2_OUT_P") (class "Default")
      (node (ref "R128") (pin "1") (pinfunction "1_1") (pintype "passive"))
    )
    (net (code "132") (name "/MYIR_CLK_OUT_N") (class "Default")
      (node (ref "R127") (pin "1") (pinfunction "1_1") (pintype "passive"))
    )
    (net (code "133") (name "/MYIR_CLK_OUT_P") (class "Default")
      (node (ref "R126") (pin "1") (pinfunction "1_1") (pintype "passive"))
    )
    (net (code "134") (name "/PS_MIO0_500") (class "Default")
      (node (ref "J2") (pin "B11") (pinfunction "11_B11") (pintype "passive+no_connect"))
    )
    (net (code "135") (name "/PS_MIO8_500") (class "Default")
      (node (ref "J2") (pin "B13") (pinfunction "13_B13") (pintype "passive+no_connect"))
    )
    (net (code "136") (name "/PS_MIO9_500") (class "Default")
      (node (ref "J2") (pin "B15") (pinfunction "15_B15") (pintype "passive+no_connect"))
    )
    (net (code "137") (name "/PS_MIO10_500") (class "Default")
      (node (ref "J2") (pin "B12") (pinfunction "12_B12") (pintype "passive"))
      (node (ref "R89") (pin "1") (pinfunction "1_1") (pintype "passive"))
    )
    (net (code "138") (name "/PS_MIO11_500") (class "Default")
      (node (ref "J2") (pin "B14") (pinfunction "14_B14") (pintype "passive"))
      (node (ref "R90") (pin "1") (pinfunction "1_1") (pintype "passive"))
    )
    (net (code "139") (name "/PS_MIO12_500") (class "Default")
      (node (ref "J2") (pin "B17") (pinfunction "17_B17") (pintype "passive+no_connect"))
    )
    (net (code "140") (name "/PS_MIO13_500") (class "Default")
      (node (ref "J2") (pin "B19") (pinfunction "19_B19") (pintype "passive+no_connect"))
    )
    (net (code "141") (name "/SPI_CLK") (class "Default")
      (node (ref "R103") (pin "2") (pinfunction "2_2") (pintype "passive"))
    )
    (net (code "142") (name "/SPI_MISO") (class "Default")
      (node (ref "R96") (pin "1") (pinfunction "1_1") (pintype "passive"))
    )
    (net (code "143") (name "/SPI_MOSI") (class "Default")
      (node (ref "R98") (pin "1") (pinfunction "1_1") (pintype "passive"))
    )
    (net (code "144") (name "/UART0_RX_MYIR") (class "Default")
      (node (ref "R89") (pin "2") (pinfunction "2_2") (pintype "passive"))
    )
    (net (code "145") (name "/UART0_TX_MYIR") (class "Default")
      (node (ref "R90") (pin "2") (pinfunction "2_2") (pintype "passive"))
    )
    (net (code "146") (name "/VDD18_KEY_BACKUP") (class "Default")
      (node (ref "J2") (pin "A5") (pinfunction "5_A5") (pintype "passive+no_connect"))
    )
    (net (code "147") (name "/XADC_INN0") (class "Default")
      (node (ref "J2") (pin "B7") (pinfunction "7_B7") (pintype "passive+no_connect"))
    )
    (net (code "148") (name "/XADC_INP0") (class "Default")
      (node (ref "J2") (pin "B5") (pinfunction "5_B5") (pintype "passive+no_connect"))
    )
    (net (code "149") (name "/XADC_VCC") (class "Default")
      (node (ref "J2") (pin "B9") (pinfunction "9_B9") (pintype "passive+no_connect"))
    )
    (net (code "150") (name "/uC_CAL_A") (class "Default")
      (node (ref "R100") (pin "2") (pinfunction "2_2") (pintype "passive"))
    )
    (net (code "151") (name "/uC_CAL_B") (class "Default")
      (node (ref "R93") (pin "2") (pinfunction "2_2") (pintype "passive"))
    )
    (net (code "152") (name "/uC_CE_A") (class "Default")
      (node (ref "R99") (pin "2") (pinfunction "2_2") (pintype "passive"))
    )
    (net (code "153") (name "/uC_CE_B") (class "Default")
      (node (ref "R91") (pin "2") (pinfunction "2_2") (pintype "passive"))
    )
    (net (code "154") (name "/uC_SH_R_A") (class "Default")
      (node (ref "R102") (pin "2") (pinfunction "2_2") (pintype "passive"))
    )
    (net (code "155") (name "/uC_SH_R_B") (class "Default")
      (node (ref "R97") (pin "2") (pinfunction "2_2") (pintype "passive"))
    )
    (net (code "156") (name "/~{SPI_CE_A}") (class "Default")
      (node (ref "R94") (pin "1") (pinfunction "1_1") (pintype "passive"))
    )
    (net (code "157") (name "/~{SPI_CE_B}") (class "Default")
      (node (ref "R92") (pin "1") (pinfunction "1_1") (pintype "passive"))
    )
    (net (code "158") (name "/~{uC_RST_A}") (class "Default")
      (node (ref "R101") (pin "2") (pinfunction "2_2") (pintype "passive"))
    )
    (net (code "159") (name "/~{uC_RST_B}") (class "Default")
      (node (ref "R95") (pin "2") (pinfunction "2_2") (pintype "passive"))
    )
    (net (code "160") (name "3V3VD") (class "Default")
      (node (ref "R124") (pin "1") (pinfunction "1_1") (pintype "passive"))
      (node (ref "R125") (pin "1") (pinfunction "1_1") (pintype "passive"))
      (node (ref "R130") (pin "1") (pinfunction "1_1") (pintype "passive"))
      (node (ref "R137") (pin "1") (pinfunction "1_1") (pintype "passive"))
      (node (ref "R138") (pin "1") (pinfunction "1_1") (pintype "passive"))
    )
    (net (code "161") (name "5VD") (class "Default")
      (node (ref "J2") (pin "A1") (pinfunction "1_A1") (pintype "passive"))
      (node (ref "J2") (pin "B1") (pinfunction "1_B1") (pintype "passive"))
    )
    (net (code "162") (name "DGND") (class "Default")
      (node (ref "J2") (pin "A2") (pinfunction "2_A2") (pintype "passive"))
      (node (ref "J2") (pin "A24") (pinfunction "24_A24") (pintype "passive"))
      (node (ref "J2") (pin "A25") (pinfunction "25_A25") (pintype "passive"))
      (node (ref "J2") (pin "A34") (pinfunction "34_A34") (pintype "passive"))
      (node (ref "J2") (pin "A35") (pinfunction "35_A35") (pintype "passive"))
      (node (ref "J2") (pin "A4") (pinfunction "4_A4") (pintype "passive"))
      (node (ref "J2") (pin "A44") (pinfunction "44_A44") (pintype "passive"))
      (node (ref "J2") (pin "A54") (pinfunction "54_A54") (pintype "passive"))
      (node (ref "J2") (pin "A67") (pinfunction "67_A67") (pintype "passive"))
      (node (ref "J2") (pin "A68") (pinfunction "68_A68") (pintype "passive"))
      (node (ref "J2") (pin "B10") (pinfunction "10_B10") (pintype "passive"))
      (node (ref "J2") (pin "B2") (pinfunction "2_B2") (pintype "passive"))
      (node (ref "J2") (pin "B20") (pinfunction "20_B20") (pintype "passive"))
      (node (ref "J2") (pin "B21") (pinfunction "21_B21") (pintype "passive"))
      (node (ref "J2") (pin "B30") (pinfunction "30_B30") (pintype "passive"))
      (node (ref "J2") (pin "B31") (pinfunction "31_B31") (pintype "passive"))
      (node (ref "J2") (pin "B4") (pinfunction "4_B4") (pintype "passive"))
      (node (ref "J2") (pin "B40") (pinfunction "40_B40") (pintype "passive"))
      (node (ref "J2") (pin "B41") (pinfunction "41_B41") (pintype "passive"))
      (node (ref "J2") (pin "B50") (pinfunction "50_B50") (pintype "passive"))
      (node (ref "J2") (pin "B60") (pinfunction "60_B60") (pintype "passive"))
      (node (ref "J2") (pin "B61") (pinfunction "61_B61") (pintype "passive"))
      (node (ref "J2") (pin "B70") (pinfunction "70_B70") (pintype "passive"))
      (node (ref "J2") (pin "B71") (pinfunction "71_B71") (pintype "passive"))
      (node (ref "J2") (pin "B80") (pinfunction "80_B80") (pintype "passive"))
    )
    (net (code "163") (name "Net-(J2A-3)") (class "Default")
      (node (ref "J2") (pin "A3") (pinfunction "3_A3") (pintype "passive"))
      (node (ref "R124") (pin "2") (pinfunction "2_2") (pintype "passive"))
    )
    (net (code "164") (name "Net-(J2A-15)") (class "Default")
      (node (ref "J2") (pin "A15") (pinfunction "15_A15") (pintype "passive"))
      (node (ref "R130") (pin "2") (pinfunction "2_2") (pintype "passive"))
    )
    (net (code "165") (name "Net-(J2A-49)") (class "Default")
      (node (ref "J2") (pin "A49") (pinfunction "49_A49") (pintype "passive"))
      (node (ref "R137") (pin "2") (pinfunction "2_2") (pintype "passive"))
    )
    (net (code "166") (name "Net-(J2B-3)") (class "Default")
      (node (ref "J2") (pin "B3") (pinfunction "3_B3") (pintype "passive"))
      (node (ref "R125") (pin "2") (pinfunction "2_2") (pintype "passive"))
    )
    (net (code "167") (name "Net-(J2B-51)") (class "Default")
      (node (ref "J2") (pin "B51") (pinfunction "51_B51") (pintype "passive"))
      (node (ref "R138") (pin "2") (pinfunction "2_2") (pintype "passive"))
    )
    (net (code "168") (name "unconnected-(J2B-16-PadB16)") (class "Default")
      (node (ref "J2") (pin "B16") (pinfunction "16_B16") (pintype "passive+no_connect"))
    )
    (net (code "169") (name "unconnected-(J2B-18-PadB18)") (class "Default")
      (node (ref "J2") (pin "B18") (pinfunction "18_B18") (pintype "passive+no_connect"))
    )
  )
)
